# microcontroller.net
KiCad netlist of a schematic drawn in Altium Designer
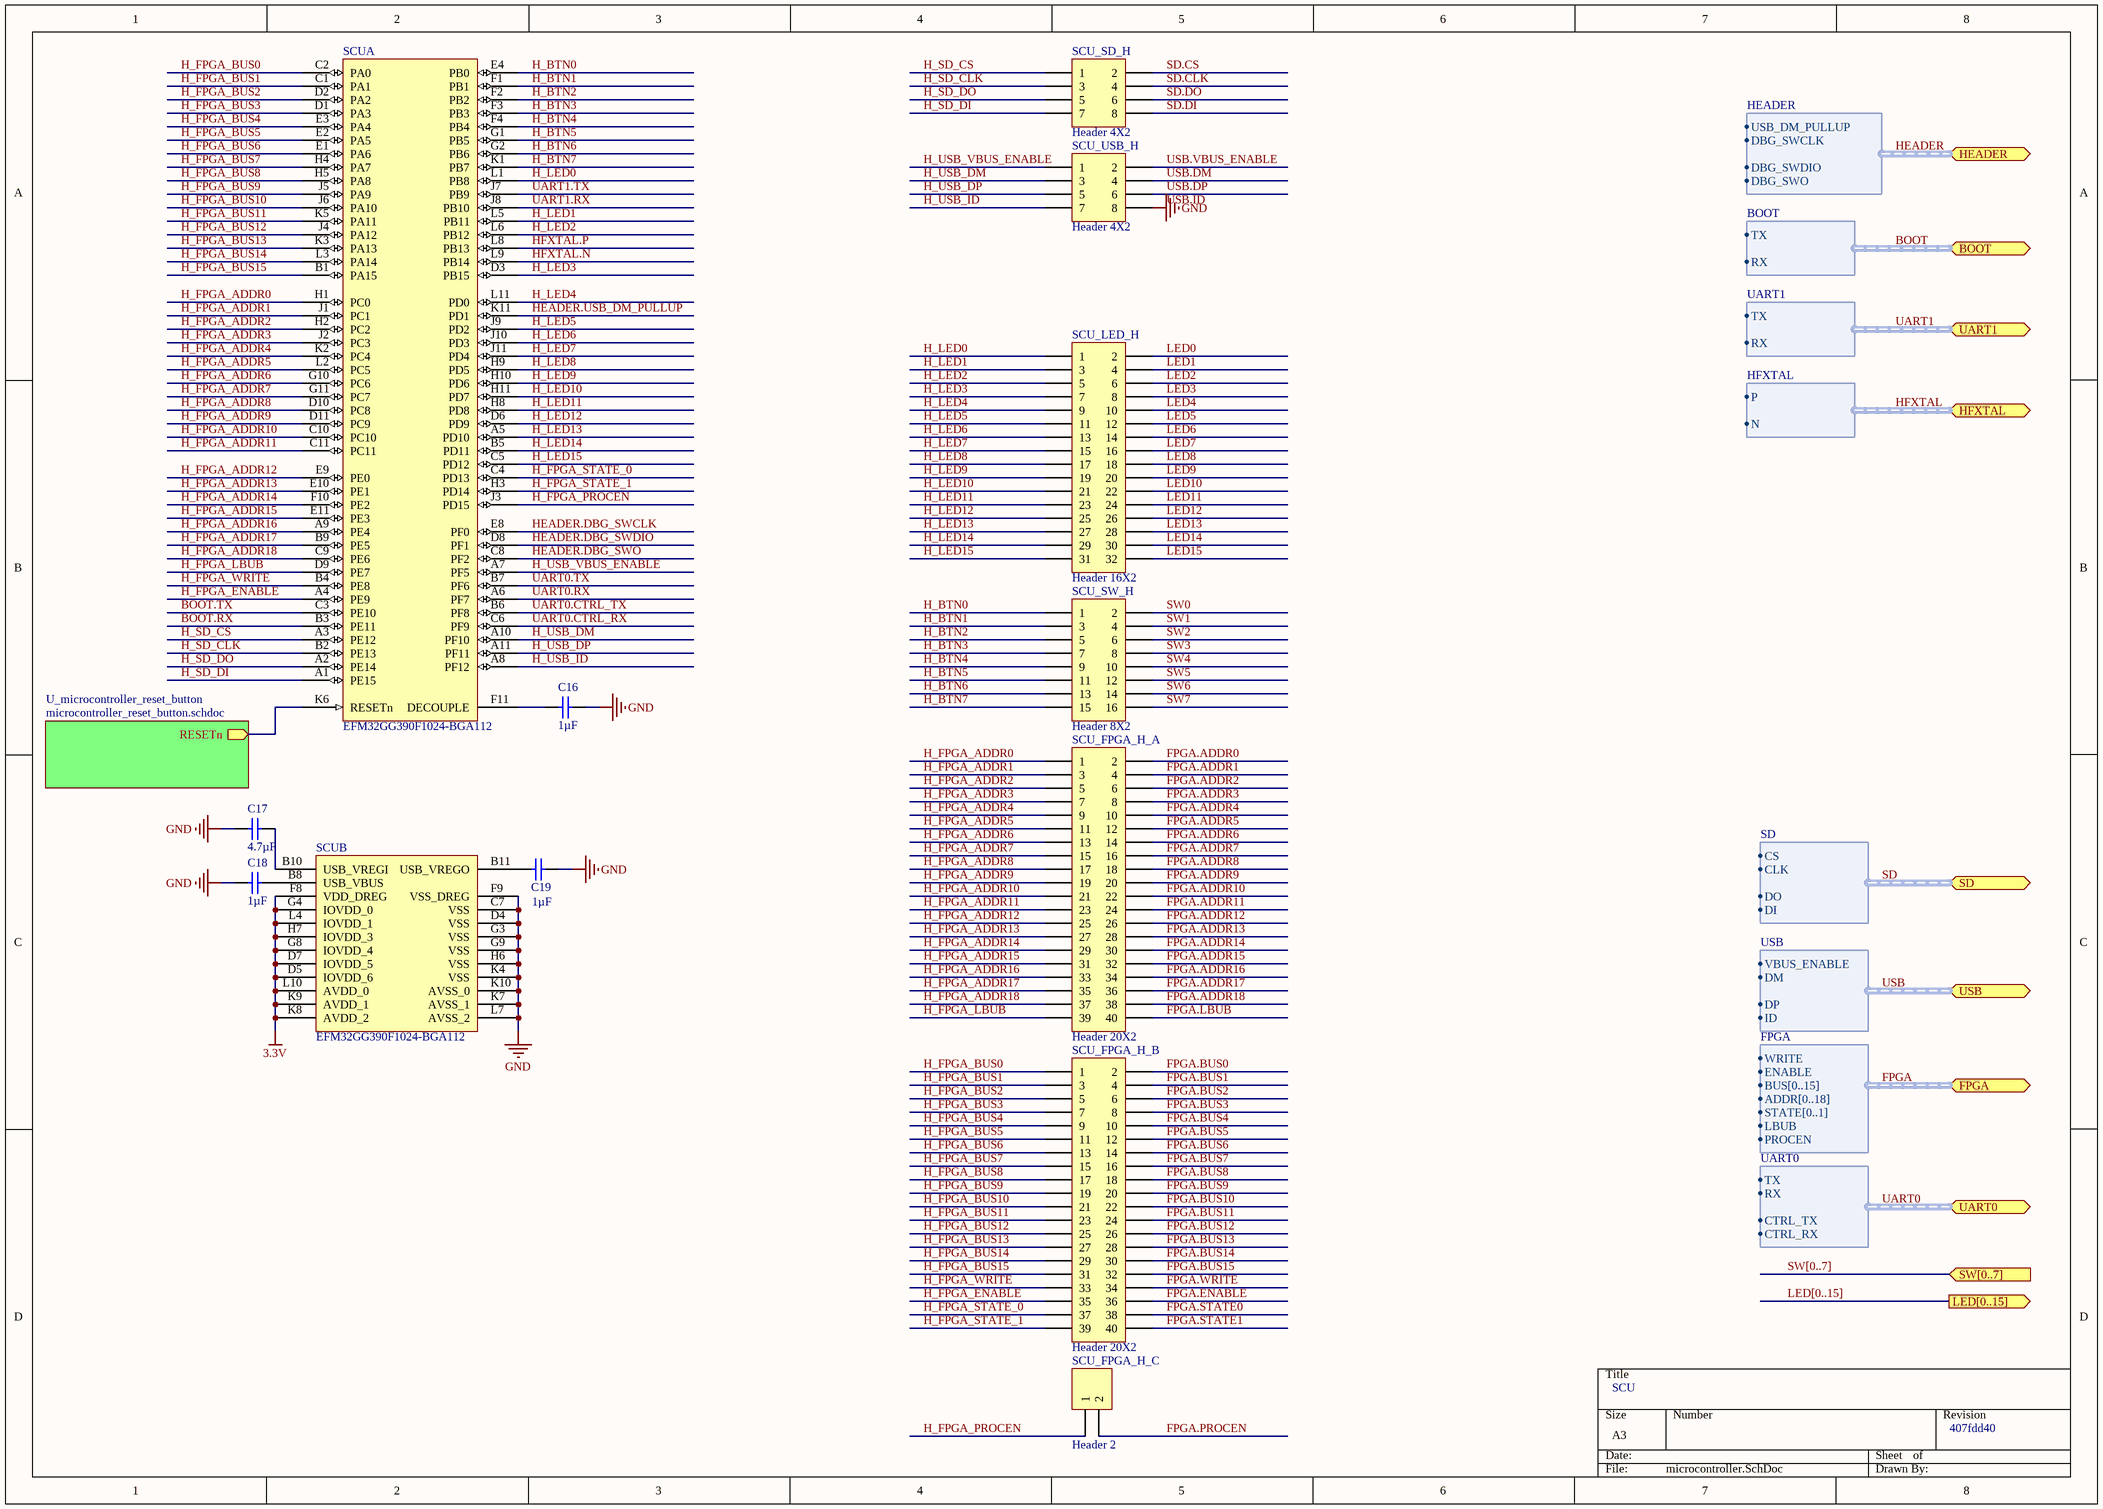
[diagram p0: microcontroller.SchDoc]

(export (version "E")
  (design (tool "Eeschema 10.0.6"))
  (components
    (comp (ref "C16")
      (value "1µF")
      (footprint "CAPC1210(3225)100_L")
      (description "CAP 1uF 100V ±0.25pF 1210 (3225 Metric) Thickness 1mm SMD")
      (fields (field (name "TOLERANCE") "±0.25pF") (field (name "Comment") "CAP 1uF 100V 1210(3225)"))
      (libsource (lib "Altium Content Vault") (part "CMP-1038-00005-1"))
    )
    (comp (ref "C17")
      (value "4.7µF")
      (footprint "CAPC1210(3225)100_L")
      (description "CAP 4.7uF 100V ±0.25pF 1210 (3225 Metric) Thickness 1mm SMD")
      (fields (field (name "TOLERANCE") "±0.25pF") (field (name "Comment") "CAP 4.7uF 100V 1210(3225)"))
      (libsource (lib "Altium Content Vault") (part "CMP-1038-00005-1"))
    )
    (comp (ref "C18")
      (value "1µF")
      (footprint "CAPC1210(3225)100_L")
      (description "CAP 1uF 100V ±0.25pF 1210 (3225 Metric) Thickness 1mm SMD")
      (fields (field (name "TOLERANCE") "±0.25pF") (field (name "Comment") "CAP 1uF 100V 1210(3225)"))
      (libsource (lib "Altium Content Vault") (part "CMP-1038-00005-1"))
    )
    (comp (ref "C19")
      (value "1µF")
      (footprint "CAPC1210(3225)100_L")
      (description "CAP 1uF 100V ±0.25pF 1210 (3225 Metric) Thickness 1mm SMD")
      (fields (field (name "TOLERANCE") "±0.25pF") (field (name "Comment") "CAP 1uF 100V 1210(3225)"))
      (libsource (lib "Altium Content Vault") (part "CMP-1038-00005-1"))
    )
    (comp (ref "SCU")
      (value "EFM32GG390F1024-BGA112")
      (footprint "ENMR-BGA112")
      (fields (field (name "GENERIC PART NUMBER") "EFM32GG390"))
      (libsource (lib "Altium Content Vault") (part "CMP-0270-00014-1"))
    )
    (comp (ref "SCU_FPGA_H_A")
      (value "Header 20X2")
      (footprint "HDR2X20")
      (description "Header, 20-Pin, Dual row")
      (fields (field (name "PUBLISHER") "Altium Limited"))
      (libsource (lib "Miscellaneous Connectors") (part "Header 20X2"))
    )
    (comp (ref "SCU_FPGA_H_B")
      (value "Header 20X2")
      (footprint "HDR2X20")
      (description "Header, 20-Pin, Dual row")
      (fields (field (name "PUBLISHER") "Altium Limited"))
      (libsource (lib "Miscellaneous Connectors") (part "Header 20X2"))
    )
    (comp (ref "SCU_FPGA_H_C")
      (value "Header 2")
      (footprint "HDR1X2")
      (description "Header, 2-Pin")
      (fields (field (name "PUBLISHER") "Altium Limited"))
      (libsource (lib "Miscellaneous Connectors") (part "Header 2"))
    )
    (comp (ref "SCU_LED_H")
      (value "Header 16X2")
      (footprint "HDR2X16")
      (description "Header, 16-Pin, Dual row")
      (fields (field (name "PUBLISHER") "Altium Limited"))
      (libsource (lib "Miscellaneous Connectors") (part "Header 16X2"))
    )
    (comp (ref "SCU_SD_H")
      (value "Header 4X2")
      (footprint "HDR2X4")
      (description "Header, 4-Pin, Dual row")
      (fields (field (name "PUBLISHER") "Altium Limited"))
      (libsource (lib "Miscellaneous Connectors") (part "Header 4X2"))
    )
    (comp (ref "SCU_SW_H")
      (value "Header 8X2")
      (footprint "HDR2X8")
      (description "Header, 8-Pin, Dual row")
      (fields (field (name "PUBLISHER") "Altium Limited"))
      (libsource (lib "Miscellaneous Connectors") (part "Header 8X2"))
    )
    (comp (ref "SCU_USB_H")
      (value "Header 4X2")
      (footprint "HDR2X4")
      (description "Header, 4-Pin, Dual row")
      (fields (field (name "PUBLISHER") "Altium Limited"))
      (libsource (lib "Miscellaneous Connectors") (part "Header 4X2"))
    )
  )
  (nets
    (net (code "9") (name "/BOOT.RX") (class "Default")
      (node (ref "SCU") (pin "B3") (pinfunction "PE11_B3") (pintype "bidirectional"))
    )
    (net (code "10") (name "/BOOT.TX") (class "Default")
      (node (ref "SCU") (pin "C3") (pinfunction "PE10_C3") (pintype "bidirectional"))
    )
    (net (code "12") (name "/FPGA.ADDR0") (class "Default")
      (node (ref "SCU_FPGA_H_A") (pin "2") (pinfunction "2_2") (pintype "passive"))
    )
    (net (code "13") (name "/FPGA.ADDR1") (class "Default")
      (node (ref "SCU_FPGA_H_A") (pin "4") (pinfunction "4_4") (pintype "passive"))
    )
    (net (code "14") (name "/FPGA.ADDR2") (class "Default")
      (node (ref "SCU_FPGA_H_A") (pin "6") (pinfunction "6_6") (pintype "passive"))
    )
    (net (code "15") (name "/FPGA.ADDR3") (class "Default")
      (node (ref "SCU_FPGA_H_A") (pin "8") (pinfunction "8_8") (pintype "passive"))
    )
    (net (code "16") (name "/FPGA.ADDR4") (class "Default")
      (node (ref "SCU_FPGA_H_A") (pin "10") (pinfunction "10_10") (pintype "passive"))
    )
    (net (code "17") (name "/FPGA.ADDR5") (class "Default")
      (node (ref "SCU_FPGA_H_A") (pin "12") (pinfunction "12_12") (pintype "passive"))
    )
    (net (code "18") (name "/FPGA.ADDR6") (class "Default")
      (node (ref "SCU_FPGA_H_A") (pin "14") (pinfunction "14_14") (pintype "passive"))
    )
    (net (code "19") (name "/FPGA.ADDR7") (class "Default")
      (node (ref "SCU_FPGA_H_A") (pin "16") (pinfunction "16_16") (pintype "passive"))
    )
    (net (code "20") (name "/FPGA.ADDR8") (class "Default")
      (node (ref "SCU_FPGA_H_A") (pin "18") (pinfunction "18_18") (pintype "passive"))
    )
    (net (code "21") (name "/FPGA.ADDR9") (class "Default")
      (node (ref "SCU_FPGA_H_A") (pin "20") (pinfunction "20_20") (pintype "passive"))
    )
    (net (code "22") (name "/FPGA.ADDR10") (class "Default")
      (node (ref "SCU_FPGA_H_A") (pin "22") (pinfunction "22_22") (pintype "passive"))
    )
    (net (code "23") (name "/FPGA.ADDR11") (class "Default")
      (node (ref "SCU_FPGA_H_A") (pin "24") (pinfunction "24_24") (pintype "passive"))
    )
    (net (code "24") (name "/FPGA.ADDR12") (class "Default")
      (node (ref "SCU_FPGA_H_A") (pin "26") (pinfunction "26_26") (pintype "passive"))
    )
    (net (code "25") (name "/FPGA.ADDR13") (class "Default")
      (node (ref "SCU_FPGA_H_A") (pin "28") (pinfunction "28_28") (pintype "passive"))
    )
    (net (code "26") (name "/FPGA.ADDR14") (class "Default")
      (node (ref "SCU_FPGA_H_A") (pin "30") (pinfunction "30_30") (pintype "passive"))
    )
    (net (code "27") (name "/FPGA.ADDR15") (class "Default")
      (node (ref "SCU_FPGA_H_A") (pin "32") (pinfunction "32_32") (pintype "passive"))
    )
    (net (code "28") (name "/FPGA.ADDR16") (class "Default")
      (node (ref "SCU_FPGA_H_A") (pin "34") (pinfunction "34_34") (pintype "passive"))
    )
    (net (code "29") (name "/FPGA.ADDR17") (class "Default")
      (node (ref "SCU_FPGA_H_A") (pin "36") (pinfunction "36_36") (pintype "passive"))
    )
    (net (code "30") (name "/FPGA.ADDR18") (class "Default")
      (node (ref "SCU_FPGA_H_A") (pin "38") (pinfunction "38_38") (pintype "passive"))
    )
    (net (code "31") (name "/FPGA.BUS0") (class "Default")
      (node (ref "SCU_FPGA_H_B") (pin "2") (pinfunction "2_2") (pintype "passive"))
    )
    (net (code "32") (name "/FPGA.BUS1") (class "Default")
      (node (ref "SCU_FPGA_H_B") (pin "4") (pinfunction "4_4") (pintype "passive"))
    )
    (net (code "33") (name "/FPGA.BUS2") (class "Default")
      (node (ref "SCU_FPGA_H_B") (pin "6") (pinfunction "6_6") (pintype "passive"))
    )
    (net (code "34") (name "/FPGA.BUS3") (class "Default")
      (node (ref "SCU_FPGA_H_B") (pin "8") (pinfunction "8_8") (pintype "passive"))
    )
    (net (code "35") (name "/FPGA.BUS4") (class "Default")
      (node (ref "SCU_FPGA_H_B") (pin "10") (pinfunction "10_10") (pintype "passive"))
    )
    (net (code "36") (name "/FPGA.BUS5") (class "Default")
      (node (ref "SCU_FPGA_H_B") (pin "12") (pinfunction "12_12") (pintype "passive"))
    )
    (net (code "37") (name "/FPGA.BUS6") (class "Default")
      (node (ref "SCU_FPGA_H_B") (pin "14") (pinfunction "14_14") (pintype "passive"))
    )
    (net (code "38") (name "/FPGA.BUS7") (class "Default")
      (node (ref "SCU_FPGA_H_B") (pin "16") (pinfunction "16_16") (pintype "passive"))
    )
    (net (code "39") (name "/FPGA.BUS8") (class "Default")
      (node (ref "SCU_FPGA_H_B") (pin "18") (pinfunction "18_18") (pintype "passive"))
    )
    (net (code "40") (name "/FPGA.BUS9") (class "Default")
      (node (ref "SCU_FPGA_H_B") (pin "20") (pinfunction "20_20") (pintype "passive"))
    )
    (net (code "41") (name "/FPGA.BUS10") (class "Default")
      (node (ref "SCU_FPGA_H_B") (pin "22") (pinfunction "22_22") (pintype "passive"))
    )
    (net (code "42") (name "/FPGA.BUS11") (class "Default")
      (node (ref "SCU_FPGA_H_B") (pin "24") (pinfunction "24_24") (pintype "passive"))
    )
    (net (code "43") (name "/FPGA.BUS12") (class "Default")
      (node (ref "SCU_FPGA_H_B") (pin "26") (pinfunction "26_26") (pintype "passive"))
    )
    (net (code "44") (name "/FPGA.BUS13") (class "Default")
      (node (ref "SCU_FPGA_H_B") (pin "28") (pinfunction "28_28") (pintype "passive"))
    )
    (net (code "45") (name "/FPGA.BUS14") (class "Default")
      (node (ref "SCU_FPGA_H_B") (pin "30") (pinfunction "30_30") (pintype "passive"))
    )
    (net (code "46") (name "/FPGA.BUS15") (class "Default")
      (node (ref "SCU_FPGA_H_B") (pin "32") (pinfunction "32_32") (pintype "passive"))
    )
    (net (code "47") (name "/FPGA.ENABLE") (class "Default")
      (node (ref "SCU_FPGA_H_B") (pin "36") (pinfunction "36_36") (pintype "passive"))
    )
    (net (code "48") (name "/FPGA.LBUB") (class "Default")
      (node (ref "SCU_FPGA_H_A") (pin "40") (pinfunction "40_40") (pintype "passive"))
    )
    (net (code "49") (name "/FPGA.PROCEN") (class "Default")
      (node (ref "SCU_FPGA_H_C") (pin "2") (pinfunction "2_2") (pintype "passive"))
    )
    (net (code "50") (name "/FPGA.STATE0") (class "Default")
      (node (ref "SCU_FPGA_H_B") (pin "38") (pinfunction "38_38") (pintype "passive"))
    )
    (net (code "51") (name "/FPGA.STATE1") (class "Default")
      (node (ref "SCU_FPGA_H_B") (pin "40") (pinfunction "40_40") (pintype "passive"))
    )
    (net (code "52") (name "/FPGA.WRITE") (class "Default")
      (node (ref "SCU_FPGA_H_B") (pin "34") (pinfunction "34_34") (pintype "passive"))
    )
    (net (code "54") (name "/HEADER.DBG_SWCLK") (class "Default")
      (node (ref "SCU") (pin "E8") (pinfunction "PF0_E8") (pintype "bidirectional"))
    )
    (net (code "55") (name "/HEADER.DBG_SWDIO") (class "Default")
      (node (ref "SCU") (pin "D8") (pinfunction "PF1_D8") (pintype "bidirectional"))
    )
    (net (code "56") (name "/HEADER.DBG_SWO") (class "Default")
      (node (ref "SCU") (pin "C8") (pinfunction "PF2_C8") (pintype "bidirectional"))
    )
    (net (code "57") (name "/HEADER.USB_DM_PULLUP") (class "Default")
      (node (ref "SCU") (pin "K11") (pinfunction "PD1_K11") (pintype "bidirectional"))
    )
    (net (code "59") (name "/HFXTAL.N") (class "Default")
      (node (ref "SCU") (pin "L9") (pinfunction "PB14_L9") (pintype "bidirectional"))
    )
    (net (code "60") (name "/HFXTAL.P") (class "Default")
      (node (ref "SCU") (pin "L8") (pinfunction "PB13_L8") (pintype "bidirectional"))
    )
    (net (code "62") (name "/H_BTN0") (class "Default")
      (node (ref "SCU") (pin "E4") (pinfunction "PB0_E4") (pintype "bidirectional"))
      (node (ref "SCU_SW_H") (pin "1") (pinfunction "1_1") (pintype "passive"))
    )
    (net (code "63") (name "/H_BTN1") (class "Default")
      (node (ref "SCU") (pin "F1") (pinfunction "PB1_F1") (pintype "bidirectional"))
      (node (ref "SCU_SW_H") (pin "3") (pinfunction "3_3") (pintype "passive"))
    )
    (net (code "64") (name "/H_BTN2") (class "Default")
      (node (ref "SCU") (pin "F2") (pinfunction "PB2_F2") (pintype "bidirectional"))
      (node (ref "SCU_SW_H") (pin "5") (pinfunction "5_5") (pintype "passive"))
    )
    (net (code "65") (name "/H_BTN3") (class "Default")
      (node (ref "SCU") (pin "F3") (pinfunction "PB3_F3") (pintype "bidirectional"))
      (node (ref "SCU_SW_H") (pin "7") (pinfunction "7_7") (pintype "passive"))
    )
    (net (code "66") (name "/H_BTN4") (class "Default")
      (node (ref "SCU") (pin "F4") (pinfunction "PB4_F4") (pintype "bidirectional"))
      (node (ref "SCU_SW_H") (pin "9") (pinfunction "9_9") (pintype "passive"))
    )
    (net (code "67") (name "/H_BTN5") (class "Default")
      (node (ref "SCU") (pin "G1") (pinfunction "PB5_G1") (pintype "bidirectional"))
      (node (ref "SCU_SW_H") (pin "11") (pinfunction "11_11") (pintype "passive"))
    )
    (net (code "68") (name "/H_BTN6") (class "Default")
      (node (ref "SCU") (pin "G2") (pinfunction "PB6_G2") (pintype "bidirectional"))
      (node (ref "SCU_SW_H") (pin "13") (pinfunction "13_13") (pintype "passive"))
    )
    (net (code "69") (name "/H_BTN7") (class "Default")
      (node (ref "SCU") (pin "K1") (pinfunction "PB7_K1") (pintype "bidirectional"))
      (node (ref "SCU_SW_H") (pin "15") (pinfunction "15_15") (pintype "passive"))
    )
    (net (code "70") (name "/H_FPGA_ADDR0") (class "Default")
      (node (ref "SCU") (pin "H1") (pinfunction "PC0_H1") (pintype "bidirectional"))
      (node (ref "SCU_FPGA_H_A") (pin "1") (pinfunction "1_1") (pintype "passive"))
    )
    (net (code "71") (name "/H_FPGA_ADDR1") (class "Default")
      (node (ref "SCU") (pin "J1") (pinfunction "PC1_J1") (pintype "bidirectional"))
      (node (ref "SCU_FPGA_H_A") (pin "3") (pinfunction "3_3") (pintype "passive"))
    )
    (net (code "72") (name "/H_FPGA_ADDR2") (class "Default")
      (node (ref "SCU") (pin "H2") (pinfunction "PC2_H2") (pintype "bidirectional"))
      (node (ref "SCU_FPGA_H_A") (pin "5") (pinfunction "5_5") (pintype "passive"))
    )
    (net (code "73") (name "/H_FPGA_ADDR3") (class "Default")
      (node (ref "SCU") (pin "J2") (pinfunction "PC3_J2") (pintype "bidirectional"))
      (node (ref "SCU_FPGA_H_A") (pin "7") (pinfunction "7_7") (pintype "passive"))
    )
    (net (code "74") (name "/H_FPGA_ADDR4") (class "Default")
      (node (ref "SCU") (pin "K2") (pinfunction "PC4_K2") (pintype "bidirectional"))
      (node (ref "SCU_FPGA_H_A") (pin "9") (pinfunction "9_9") (pintype "passive"))
    )
    (net (code "75") (name "/H_FPGA_ADDR5") (class "Default")
      (node (ref "SCU") (pin "L2") (pinfunction "PC5_L2") (pintype "bidirectional"))
      (node (ref "SCU_FPGA_H_A") (pin "11") (pinfunction "11_11") (pintype "passive"))
    )
    (net (code "76") (name "/H_FPGA_ADDR6") (class "Default")
      (node (ref "SCU") (pin "G10") (pinfunction "PC6_G10") (pintype "bidirectional"))
      (node (ref "SCU_FPGA_H_A") (pin "13") (pinfunction "13_13") (pintype "passive"))
    )
    (net (code "77") (name "/H_FPGA_ADDR7") (class "Default")
      (node (ref "SCU") (pin "G11") (pinfunction "PC7_G11") (pintype "bidirectional"))
      (node (ref "SCU_FPGA_H_A") (pin "15") (pinfunction "15_15") (pintype "passive"))
    )
    (net (code "78") (name "/H_FPGA_ADDR8") (class "Default")
      (node (ref "SCU") (pin "D10") (pinfunction "PC8_D10") (pintype "bidirectional"))
      (node (ref "SCU_FPGA_H_A") (pin "17") (pinfunction "17_17") (pintype "passive"))
    )
    (net (code "79") (name "/H_FPGA_ADDR9") (class "Default")
      (node (ref "SCU") (pin "D11") (pinfunction "PC9_D11") (pintype "bidirectional"))
      (node (ref "SCU_FPGA_H_A") (pin "19") (pinfunction "19_19") (pintype "passive"))
    )
    (net (code "80") (name "/H_FPGA_ADDR10") (class "Default")
      (node (ref "SCU") (pin "C10") (pinfunction "PC10_C10") (pintype "bidirectional"))
      (node (ref "SCU_FPGA_H_A") (pin "21") (pinfunction "21_21") (pintype "passive"))
    )
    (net (code "81") (name "/H_FPGA_ADDR11") (class "Default")
      (node (ref "SCU") (pin "C11") (pinfunction "PC11_C11") (pintype "bidirectional"))
      (node (ref "SCU_FPGA_H_A") (pin "23") (pinfunction "23_23") (pintype "passive"))
    )
    (net (code "82") (name "/H_FPGA_ADDR12") (class "Default")
      (node (ref "SCU") (pin "E9") (pinfunction "PE0_E9") (pintype "bidirectional"))
      (node (ref "SCU_FPGA_H_A") (pin "25") (pinfunction "25_25") (pintype "passive"))
    )
    (net (code "83") (name "/H_FPGA_ADDR13") (class "Default")
      (node (ref "SCU") (pin "E10") (pinfunction "PE1_E10") (pintype "bidirectional"))
      (node (ref "SCU_FPGA_H_A") (pin "27") (pinfunction "27_27") (pintype "passive"))
    )
    (net (code "84") (name "/H_FPGA_ADDR14") (class "Default")
      (node (ref "SCU") (pin "F10") (pinfunction "PE2_F10") (pintype "bidirectional"))
      (node (ref "SCU_FPGA_H_A") (pin "29") (pinfunction "29_29") (pintype "passive"))
    )
    (net (code "85") (name "/H_FPGA_ADDR15") (class "Default")
      (node (ref "SCU") (pin "E11") (pinfunction "PE3_E11") (pintype "bidirectional"))
      (node (ref "SCU_FPGA_H_A") (pin "31") (pinfunction "31_31") (pintype "passive"))
    )
    (net (code "86") (name "/H_FPGA_ADDR16") (class "Default")
      (node (ref "SCU") (pin "A9") (pinfunction "PE4_A9") (pintype "bidirectional"))
      (node (ref "SCU_FPGA_H_A") (pin "33") (pinfunction "33_33") (pintype "passive"))
    )
    (net (code "87") (name "/H_FPGA_ADDR17") (class "Default")
      (node (ref "SCU") (pin "B9") (pinfunction "PE5_B9") (pintype "bidirectional"))
      (node (ref "SCU_FPGA_H_A") (pin "35") (pinfunction "35_35") (pintype "passive"))
    )
    (net (code "88") (name "/H_FPGA_ADDR18") (class "Default")
      (node (ref "SCU") (pin "C9") (pinfunction "PE6_C9") (pintype "bidirectional"))
      (node (ref "SCU_FPGA_H_A") (pin "37") (pinfunction "37_37") (pintype "passive"))
    )
    (net (code "89") (name "/H_FPGA_BUS0") (class "Default")
      (node (ref "SCU") (pin "C2") (pinfunction "PA0_C2") (pintype "bidirectional"))
      (node (ref "SCU_FPGA_H_B") (pin "1") (pinfunction "1_1") (pintype "passive"))
    )
    (net (code "90") (name "/H_FPGA_BUS1") (class "Default")
      (node (ref "SCU") (pin "C1") (pinfunction "PA1_C1") (pintype "bidirectional"))
      (node (ref "SCU_FPGA_H_B") (pin "3") (pinfunction "3_3") (pintype "passive"))
    )
    (net (code "91") (name "/H_FPGA_BUS2") (class "Default")
      (node (ref "SCU") (pin "D2") (pinfunction "PA2_D2") (pintype "bidirectional"))
      (node (ref "SCU_FPGA_H_B") (pin "5") (pinfunction "5_5") (pintype "passive"))
    )
    (net (code "92") (name "/H_FPGA_BUS3") (class "Default")
      (node (ref "SCU") (pin "D1") (pinfunction "PA3_D1") (pintype "bidirectional"))
      (node (ref "SCU_FPGA_H_B") (pin "7") (pinfunction "7_7") (pintype "passive"))
    )
    (net (code "93") (name "/H_FPGA_BUS4") (class "Default")
      (node (ref "SCU") (pin "E3") (pinfunction "PA4_E3") (pintype "bidirectional"))
      (node (ref "SCU_FPGA_H_B") (pin "9") (pinfunction "9_9") (pintype "passive"))
    )
    (net (code "94") (name "/H_FPGA_BUS5") (class "Default")
      (node (ref "SCU") (pin "E2") (pinfunction "PA5_E2") (pintype "bidirectional"))
      (node (ref "SCU_FPGA_H_B") (pin "11") (pinfunction "11_11") (pintype "passive"))
    )
    (net (code "95") (name "/H_FPGA_BUS6") (class "Default")
      (node (ref "SCU") (pin "E1") (pinfunction "PA6_E1") (pintype "bidirectional"))
      (node (ref "SCU_FPGA_H_B") (pin "13") (pinfunction "13_13") (pintype "passive"))
    )
    (net (code "96") (name "/H_FPGA_BUS7") (class "Default")
      (node (ref "SCU") (pin "H4") (pinfunction "PA7_H4") (pintype "bidirectional"))
      (node (ref "SCU_FPGA_H_B") (pin "15") (pinfunction "15_15") (pintype "passive"))
    )
    (net (code "97") (name "/H_FPGA_BUS8") (class "Default")
      (node (ref "SCU") (pin "H5") (pinfunction "PA8_H5") (pintype "bidirectional"))
      (node (ref "SCU_FPGA_H_B") (pin "17") (pinfunction "17_17") (pintype "passive"))
    )
    (net (code "98") (name "/H_FPGA_BUS9") (class "Default")
      (node (ref "SCU") (pin "J5") (pinfunction "PA9_J5") (pintype "bidirectional"))
      (node (ref "SCU_FPGA_H_B") (pin "19") (pinfunction "19_19") (pintype "passive"))
    )
    (net (code "99") (name "/H_FPGA_BUS10") (class "Default")
      (node (ref "SCU") (pin "J6") (pinfunction "PA10_J6") (pintype "bidirectional"))
      (node (ref "SCU_FPGA_H_B") (pin "21") (pinfunction "21_21") (pintype "passive"))
    )
    (net (code "100") (name "/H_FPGA_BUS11") (class "Default")
      (node (ref "SCU") (pin "K5") (pinfunction "PA11_K5") (pintype "bidirectional"))
      (node (ref "SCU_FPGA_H_B") (pin "23") (pinfunction "23_23") (pintype "passive"))
    )
    (net (code "101") (name "/H_FPGA_BUS12") (class "Default")
      (node (ref "SCU") (pin "J4") (pinfunction "PA12_J4") (pintype "bidirectional"))
      (node (ref "SCU_FPGA_H_B") (pin "25") (pinfunction "25_25") (pintype "passive"))
    )
    (net (code "102") (name "/H_FPGA_BUS13") (class "Default")
      (node (ref "SCU") (pin "K3") (pinfunction "PA13_K3") (pintype "bidirectional"))
      (node (ref "SCU_FPGA_H_B") (pin "27") (pinfunction "27_27") (pintype "passive"))
    )
    (net (code "103") (name "/H_FPGA_BUS14") (class "Default")
      (node (ref "SCU") (pin "L3") (pinfunction "PA14_L3") (pintype "bidirectional"))
      (node (ref "SCU_FPGA_H_B") (pin "29") (pinfunction "29_29") (pintype "passive"))
    )
    (net (code "104") (name "/H_FPGA_BUS15") (class "Default")
      (node (ref "SCU") (pin "B1") (pinfunction "PA15_B1") (pintype "bidirectional"))
      (node (ref "SCU_FPGA_H_B") (pin "31") (pinfunction "31_31") (pintype "passive"))
    )
    (net (code "105") (name "/H_FPGA_ENABLE") (class "Default")
      (node (ref "SCU") (pin "A4") (pinfunction "PE9_A4") (pintype "bidirectional"))
      (node (ref "SCU_FPGA_H_B") (pin "35") (pinfunction "35_35") (pintype "passive"))
    )
    (net (code "106") (name "/H_FPGA_LBUB") (class "Default")
      (node (ref "SCU") (pin "D9") (pinfunction "PE7_D9") (pintype "bidirectional"))
      (node (ref "SCU_FPGA_H_A") (pin "39") (pinfunction "39_39") (pintype "passive"))
    )
    (net (code "107") (name "/H_FPGA_PROCEN") (class "Default")
      (node (ref "SCU") (pin "J3") (pinfunction "PD15_J3") (pintype "bidirectional"))
      (node (ref "SCU_FPGA_H_C") (pin "1") (pinfunction "1_1") (pintype "passive"))
    )
    (net (code "108") (name "/H_FPGA_STATE_0") (class "Default")
      (node (ref "SCU") (pin "C4") (pinfunction "PD13_C4") (pintype "bidirectional"))
      (node (ref "SCU_FPGA_H_B") (pin "37") (pinfunction "37_37") (pintype "passive"))
    )
    (net (code "109") (name "/H_FPGA_STATE_1") (class "Default")
      (node (ref "SCU") (pin "H3") (pinfunction "PD14_H3") (pintype "bidirectional"))
      (node (ref "SCU_FPGA_H_B") (pin "39") (pinfunction "39_39") (pintype "passive"))
    )
    (net (code "110") (name "/H_FPGA_WRITE") (class "Default")
      (node (ref "SCU") (pin "B4") (pinfunction "PE8_B4") (pintype "bidirectional"))
      (node (ref "SCU_FPGA_H_B") (pin "33") (pinfunction "33_33") (pintype "passive"))
    )
    (net (code "111") (name "/H_LED0") (class "Default")
      (node (ref "SCU") (pin "L1") (pinfunction "PB8_L1") (pintype "bidirectional"))
      (node (ref "SCU_LED_H") (pin "1") (pinfunction "1_1") (pintype "passive"))
    )
    (net (code "112") (name "/H_LED1") (class "Default")
      (node (ref "SCU") (pin "L5") (pinfunction "PB11_L5") (pintype "bidirectional"))
      (node (ref "SCU_LED_H") (pin "3") (pinfunction "3_3") (pintype "passive"))
    )
    (net (code "113") (name "/H_LED2") (class "Default")
      (node (ref "SCU") (pin "L6") (pinfunction "PB12_L6") (pintype "bidirectional"))
      (node (ref "SCU_LED_H") (pin "5") (pinfunction "5_5") (pintype "passive"))
    )
    (net (code "114") (name "/H_LED3") (class "Default")
      (node (ref "SCU") (pin "D3") (pinfunction "PB15_D3") (pintype "bidirectional"))
      (node (ref "SCU_LED_H") (pin "7") (pinfunction "7_7") (pintype "passive"))
    )
    (net (code "115") (name "/H_LED4") (class "Default")
      (node (ref "SCU") (pin "L11") (pinfunction "PD0_L11") (pintype "bidirectional"))
      (node (ref "SCU_LED_H") (pin "9") (pinfunction "9_9") (pintype "passive"))
    )
    (net (code "116") (name "/H_LED5") (class "Default")
      (node (ref "SCU") (pin "J9") (pinfunction "PD2_J9") (pintype "bidirectional"))
      (node (ref "SCU_LED_H") (pin "11") (pinfunction "11_11") (pintype "passive"))
    )
    (net (code "117") (name "/H_LED6") (class "Default")
      (node (ref "SCU") (pin "J10") (pinfunction "PD3_J10") (pintype "bidirectional"))
      (node (ref "SCU_LED_H") (pin "13") (pinfunction "13_13") (pintype "passive"))
    )
    (net (code "118") (name "/H_LED7") (class "Default")
      (node (ref "SCU") (pin "J11") (pinfunction "PD4_J11") (pintype "bidirectional"))
      (node (ref "SCU_LED_H") (pin "15") (pinfunction "15_15") (pintype "passive"))
    )
    (net (code "119") (name "/H_LED8") (class "Default")
      (node (ref "SCU") (pin "H9") (pinfunction "PD5_H9") (pintype "bidirectional"))
      (node (ref "SCU_LED_H") (pin "17") (pinfunction "17_17") (pintype "passive"))
    )
    (net (code "120") (name "/H_LED9") (class "Default")
      (node (ref "SCU") (pin "H10") (pinfunction "PD6_H10") (pintype "bidirectional"))
      (node (ref "SCU_LED_H") (pin "19") (pinfunction "19_19") (pintype "passive"))
    )
    (net (code "121") (name "/H_LED10") (class "Default")
      (node (ref "SCU") (pin "H11") (pinfunction "PD7_H11") (pintype "bidirectional"))
      (node (ref "SCU_LED_H") (pin "21") (pinfunction "21_21") (pintype "passive"))
    )
    (net (code "122") (name "/H_LED11") (class "Default")
      (node (ref "SCU") (pin "H8") (pinfunction "PD8_H8") (pintype "bidirectional"))
      (node (ref "SCU_LED_H") (pin "23") (pinfunction "23_23") (pintype "passive"))
    )
    (net (code "123") (name "/H_LED12") (class "Default")
      (node (ref "SCU") (pin "D6") (pinfunction "PD9_D6") (pintype "bidirectional"))
      (node (ref "SCU_LED_H") (pin "25") (pinfunction "25_25") (pintype "passive"))
    )
    (net (code "124") (name "/H_LED13") (class "Default")
      (node (ref "SCU") (pin "A5") (pinfunction "PD10_A5") (pintype "bidirectional"))
      (node (ref "SCU_LED_H") (pin "27") (pinfunction "27_27") (pintype "passive"))
    )
    (net (code "125") (name "/H_LED14") (class "Default")
      (node (ref "SCU") (pin "B5") (pinfunction "PD11_B5") (pintype "bidirectional"))
      (node (ref "SCU_LED_H") (pin "29") (pinfunction "29_29") (pintype "passive"))
    )
    (net (code "126") (name "/H_LED15") (class "Default")
      (node (ref "SCU") (pin "C5") (pinfunction "PD12_C5") (pintype "bidirectional"))
      (node (ref "SCU_LED_H") (pin "31") (pinfunction "31_31") (pintype "passive"))
    )
    (net (code "127") (name "/H_SD_CLK") (class "Default")
      (node (ref "SCU") (pin "B2") (pinfunction "PE13_B2") (pintype "bidirectional"))
      (node (ref "SCU_SD_H") (pin "3") (pinfunction "3_3") (pintype "passive"))
    )
    (net (code "128") (name "/H_SD_CS") (class "Default")
      (node (ref "SCU") (pin "A3") (pinfunction "PE12_A3") (pintype "bidirectional"))
      (node (ref "SCU_SD_H") (pin "1") (pinfunction "1_1") (pintype "passive"))
    )
    (net (code "129") (name "/H_SD_DI") (class "Default")
      (node (ref "SCU") (pin "A1") (pinfunction "PE15_A1") (pintype "bidirectional"))
      (node (ref "SCU_SD_H") (pin "7") (pinfunction "7_7") (pintype "passive"))
    )
    (net (code "130") (name "/H_SD_DO") (class "Default")
      (node (ref "SCU") (pin "A2") (pinfunction "PE14_A2") (pintype "bidirectional"))
      (node (ref "SCU_SD_H") (pin "5") (pinfunction "5_5") (pintype "passive"))
    )
    (net (code "131") (name "/H_USB_DM") (class "Default")
      (node (ref "SCU") (pin "A10") (pinfunction "PF10_A10") (pintype "bidirectional"))
      (node (ref "SCU_USB_H") (pin "3") (pinfunction "3_3") (pintype "passive"))
    )
    (net (code "132") (name "/H_USB_DP") (class "Default")
      (node (ref "SCU") (pin "A11") (pinfunction "PF11_A11") (pintype "bidirectional"))
      (node (ref "SCU_USB_H") (pin "5") (pinfunction "5_5") (pintype "passive"))
    )
    (net (code "133") (name "/H_USB_ID") (class "Default")
      (node (ref "SCU") (pin "A8") (pinfunction "PF12_A8") (pintype "bidirectional"))
      (node (ref "SCU_USB_H") (pin "7") (pinfunction "7_7") (pintype "passive"))
    )
    (net (code "134") (name "/H_USB_VBUS_ENABLE") (class "Default")
      (node (ref "SCU") (pin "A7") (pinfunction "PF5_A7") (pintype "bidirectional"))
      (node (ref "SCU_USB_H") (pin "1") (pinfunction "1_1") (pintype "passive"))
    )
    (net (code "135") (name "/LED0") (class "Default")
      (node (ref "SCU_LED_H") (pin "2") (pinfunction "2_2") (pintype "passive"))
    )
    (net (code "136") (name "/LED1") (class "Default")
      (node (ref "SCU_LED_H") (pin "4") (pinfunction "4_4") (pintype "passive"))
    )
    (net (code "137") (name "/LED2") (class "Default")
      (node (ref "SCU_LED_H") (pin "6") (pinfunction "6_6") (pintype "passive"))
    )
    (net (code "138") (name "/LED3") (class "Default")
      (node (ref "SCU_LED_H") (pin "8") (pinfunction "8_8") (pintype "passive"))
    )
    (net (code "139") (name "/LED4") (class "Default")
      (node (ref "SCU_LED_H") (pin "10") (pinfunction "10_10") (pintype "passive"))
    )
    (net (code "140") (name "/LED5") (class "Default")
      (node (ref "SCU_LED_H") (pin "12") (pinfunction "12_12") (pintype "passive"))
    )
    (net (code "141") (name "/LED6") (class "Default")
      (node (ref "SCU_LED_H") (pin "14") (pinfunction "14_14") (pintype "passive"))
    )
    (net (code "142") (name "/LED7") (class "Default")
      (node (ref "SCU_LED_H") (pin "16") (pinfunction "16_16") (pintype "passive"))
    )
    (net (code "143") (name "/LED8") (class "Default")
      (node (ref "SCU_LED_H") (pin "18") (pinfunction "18_18") (pintype "passive"))
    )
    (net (code "144") (name "/LED9") (class "Default")
      (node (ref "SCU_LED_H") (pin "20") (pinfunction "20_20") (pintype "passive"))
    )
    (net (code "145") (name "/LED10") (class "Default")
      (node (ref "SCU_LED_H") (pin "22") (pinfunction "22_22") (pintype "passive"))
    )
    (net (code "146") (name "/LED11") (class "Default")
      (node (ref "SCU_LED_H") (pin "24") (pinfunction "24_24") (pintype "passive"))
    )
    (net (code "147") (name "/LED12") (class "Default")
      (node (ref "SCU_LED_H") (pin "26") (pinfunction "26_26") (pintype "passive"))
    )
    (net (code "148") (name "/LED13") (class "Default")
      (node (ref "SCU_LED_H") (pin "28") (pinfunction "28_28") (pintype "passive"))
    )
    (net (code "149") (name "/LED14") (class "Default")
      (node (ref "SCU_LED_H") (pin "30") (pinfunction "30_30") (pintype "passive"))
    )
    (net (code "150") (name "/LED15") (class "Default")
      (node (ref "SCU_LED_H") (pin "32") (pinfunction "32_32") (pintype "passive"))
    )
    (net (code "152") (name "/RESETn") (class "Default")
      (node (ref "SCU") (pin "K6") (pinfunction "RESETn_K6") (pintype "input"))
    )
    (net (code "153") (name "/SD.CLK") (class "Default")
      (node (ref "SCU_SD_H") (pin "4") (pinfunction "4_4") (pintype "passive"))
    )
    (net (code "154") (name "/SD.CS") (class "Default")
      (node (ref "SCU_SD_H") (pin "2") (pinfunction "2_2") (pintype "passive"))
    )
    (net (code "155") (name "/SD.DI") (class "Default")
      (node (ref "SCU_SD_H") (pin "8") (pinfunction "8_8") (pintype "passive"))
    )
    (net (code "156") (name "/SD.DO") (class "Default")
      (node (ref "SCU_SD_H") (pin "6") (pinfunction "6_6") (pintype "passive"))
    )
    (net (code "158") (name "/SW0") (class "Default")
      (node (ref "SCU_SW_H") (pin "2") (pinfunction "2_2") (pintype "passive"))
    )
    (net (code "159") (name "/SW1") (class "Default")
      (node (ref "SCU_SW_H") (pin "4") (pinfunction "4_4") (pintype "passive"))
    )
    (net (code "160") (name "/SW2") (class "Default")
      (node (ref "SCU_SW_H") (pin "6") (pinfunction "6_6") (pintype "passive"))
    )
    (net (code "161") (name "/SW3") (class "Default")
      (node (ref "SCU_SW_H") (pin "8") (pinfunction "8_8") (pintype "passive"))
    )
    (net (code "162") (name "/SW4") (class "Default")
      (node (ref "SCU_SW_H") (pin "10") (pinfunction "10_10") (pintype "passive"))
    )
    (net (code "163") (name "/SW5") (class "Default")
      (node (ref "SCU_SW_H") (pin "12") (pinfunction "12_12") (pintype "passive"))
    )
    (net (code "164") (name "/SW6") (class "Default")
      (node (ref "SCU_SW_H") (pin "14") (pinfunction "14_14") (pintype "passive"))
    )
    (net (code "165") (name "/SW7") (class "Default")
      (node (ref "SCU_SW_H") (pin "16") (pinfunction "16_16") (pintype "passive"))
    )
    (net (code "167") (name "/UART0.CTRL_RX") (class "Default")
      (node (ref "SCU") (pin "C6") (pinfunction "PF9_C6") (pintype "bidirectional"))
    )
    (net (code "168") (name "/UART0.CTRL_TX") (class "Default")
      (node (ref "SCU") (pin "B6") (pinfunction "PF8_B6") (pintype "bidirectional"))
    )
    (net (code "169") (name "/UART0.RX") (class "Default")
      (node (ref "SCU") (pin "A6") (pinfunction "PF7_A6") (pintype "bidirectional"))
    )
    (net (code "170") (name "/UART0.TX") (class "Default")
      (node (ref "SCU") (pin "B7") (pinfunction "PF6_B7") (pintype "bidirectional"))
    )
    (net (code "172") (name "/UART1.RX") (class "Default")
      (node (ref "SCU") (pin "J8") (pinfunction "PB10_J8") (pintype "bidirectional"))
    )
    (net (code "173") (name "/UART1.TX") (class "Default")
      (node (ref "SCU") (pin "J7") (pinfunction "PB9_J7") (pintype "bidirectional"))
    )
    (net (code "175") (name "/USB.DM") (class "Default")
      (node (ref "SCU_USB_H") (pin "4") (pinfunction "4_4") (pintype "passive"))
    )
    (net (code "176") (name "/USB.DP") (class "Default")
      (node (ref "SCU_USB_H") (pin "6") (pinfunction "6_6") (pintype "passive"))
    )
    (net (code "178") (name "/USB.VBUS_ENABLE") (class "Default")
      (node (ref "SCU_USB_H") (pin "2") (pinfunction "2_2") (pintype "passive"))
    )
    (net (code "180") (name "3.3V") (class "Default")
      (node (ref "SCU") (pin "D5") (pinfunction "IOVDD_6_D5") (pintype "power_in"))
      (node (ref "SCU") (pin "D7") (pinfunction "IOVDD_5_D7") (pintype "power_in"))
      (node (ref "SCU") (pin "F8") (pinfunction "VDD_DREG_F8") (pintype "power_in"))
      (node (ref "SCU") (pin "G4") (pinfunction "IOVDD_0_G4") (pintype "power_in"))
      (node (ref "SCU") (pin "G8") (pinfunction "IOVDD_4_G8") (pintype "power_in"))
      (node (ref "SCU") (pin "H7") (pinfunction "IOVDD_3_H7") (pintype "power_in"))
      (node (ref "SCU") (pin "K8") (pinfunction "AVDD_2_K8") (pintype "power_in"))
      (node (ref "SCU") (pin "K9") (pinfunction "AVDD_1_K9") (pintype "power_in"))
      (node (ref "SCU") (pin "L10") (pinfunction "AVDD_0_L10") (pintype "power_in"))
      (node (ref "SCU") (pin "L4") (pinfunction "IOVDD_1_L4") (pintype "power_in"))
    )
    (net (code "181") (name "GND") (class "Default")
      (node (ref "C16") (pin "2") (pinfunction "2_2") (pintype "passive"))
      (node (ref "C17") (pin "2") (pinfunction "2_2") (pintype "passive"))
      (node (ref "C18") (pin "2") (pinfunction "2_2") (pintype "passive"))
      (node (ref "C19") (pin "2") (pinfunction "2_2") (pintype "passive"))
      (node (ref "SCU") (pin "C7") (pinfunction "VSS_C7") (pintype "power_in"))
      (node (ref "SCU") (pin "D4") (pinfunction "VSS_D4") (pintype "power_in"))
      (node (ref "SCU") (pin "F9") (pinfunction "VSS_DREG_F9") (pintype "power_in"))
      (node (ref "SCU") (pin "G3") (pinfunction "VSS_G3") (pintype "power_in"))
      (node (ref "SCU") (pin "G9") (pinfunction "VSS_G9") (pintype "power_in"))
      (node (ref "SCU") (pin "H6") (pinfunction "VSS_H6") (pintype "power_in"))
      (node (ref "SCU") (pin "K10") (pinfunction "AVSS_0_K10") (pintype "power_in"))
      (node (ref "SCU") (pin "K4") (pinfunction "VSS_K4") (pintype "power_in"))
      (node (ref "SCU") (pin "K7") (pinfunction "AVSS_1_K7") (pintype "power_in"))
      (node (ref "SCU") (pin "L7") (pinfunction "AVSS_2_L7") (pintype "power_in"))
      (node (ref "SCU_USB_H") (pin "8") (pinfunction "8_8") (pintype "passive"))
    )
    (net (code "182") (name "Net-(SCUA-DECOUPLE)") (class "Default")
      (node (ref "C16") (pin "1") (pinfunction "1_1") (pintype "passive"))
      (node (ref "SCU") (pin "F11") (pinfunction "DECOUPLE_F11") (pintype "passive"))
    )
    (net (code "183") (name "Net-(SCUB-USB_VBUS)") (class "Default")
      (node (ref "C18") (pin "1") (pinfunction "1_1") (pintype "passive"))
      (node (ref "SCU") (pin "B8") (pinfunction "USB_VBUS_B8") (pintype "power_in"))
    )
    (net (code "184") (name "Net-(SCUB-USB_VREGI)") (class "Default")
      (node (ref "C17") (pin "1") (pinfunction "1_1") (pintype "passive"))
      (node (ref "SCU") (pin "B10") (pinfunction "USB_VREGI_B10") (pintype "power_in"))
    )
    (net (code "185") (name "Net-(SCUB-USB_VREGO)") (class "Default")
      (node (ref "C19") (pin "1") (pinfunction "1_1") (pintype "passive"))
      (node (ref "SCU") (pin "B11") (pinfunction "USB_VREGO_B11") (pintype "passive"))
    )
  )
)
